# Green_Pill_stlink.net
KiCad netlist of a schematic drawn in EAGLE
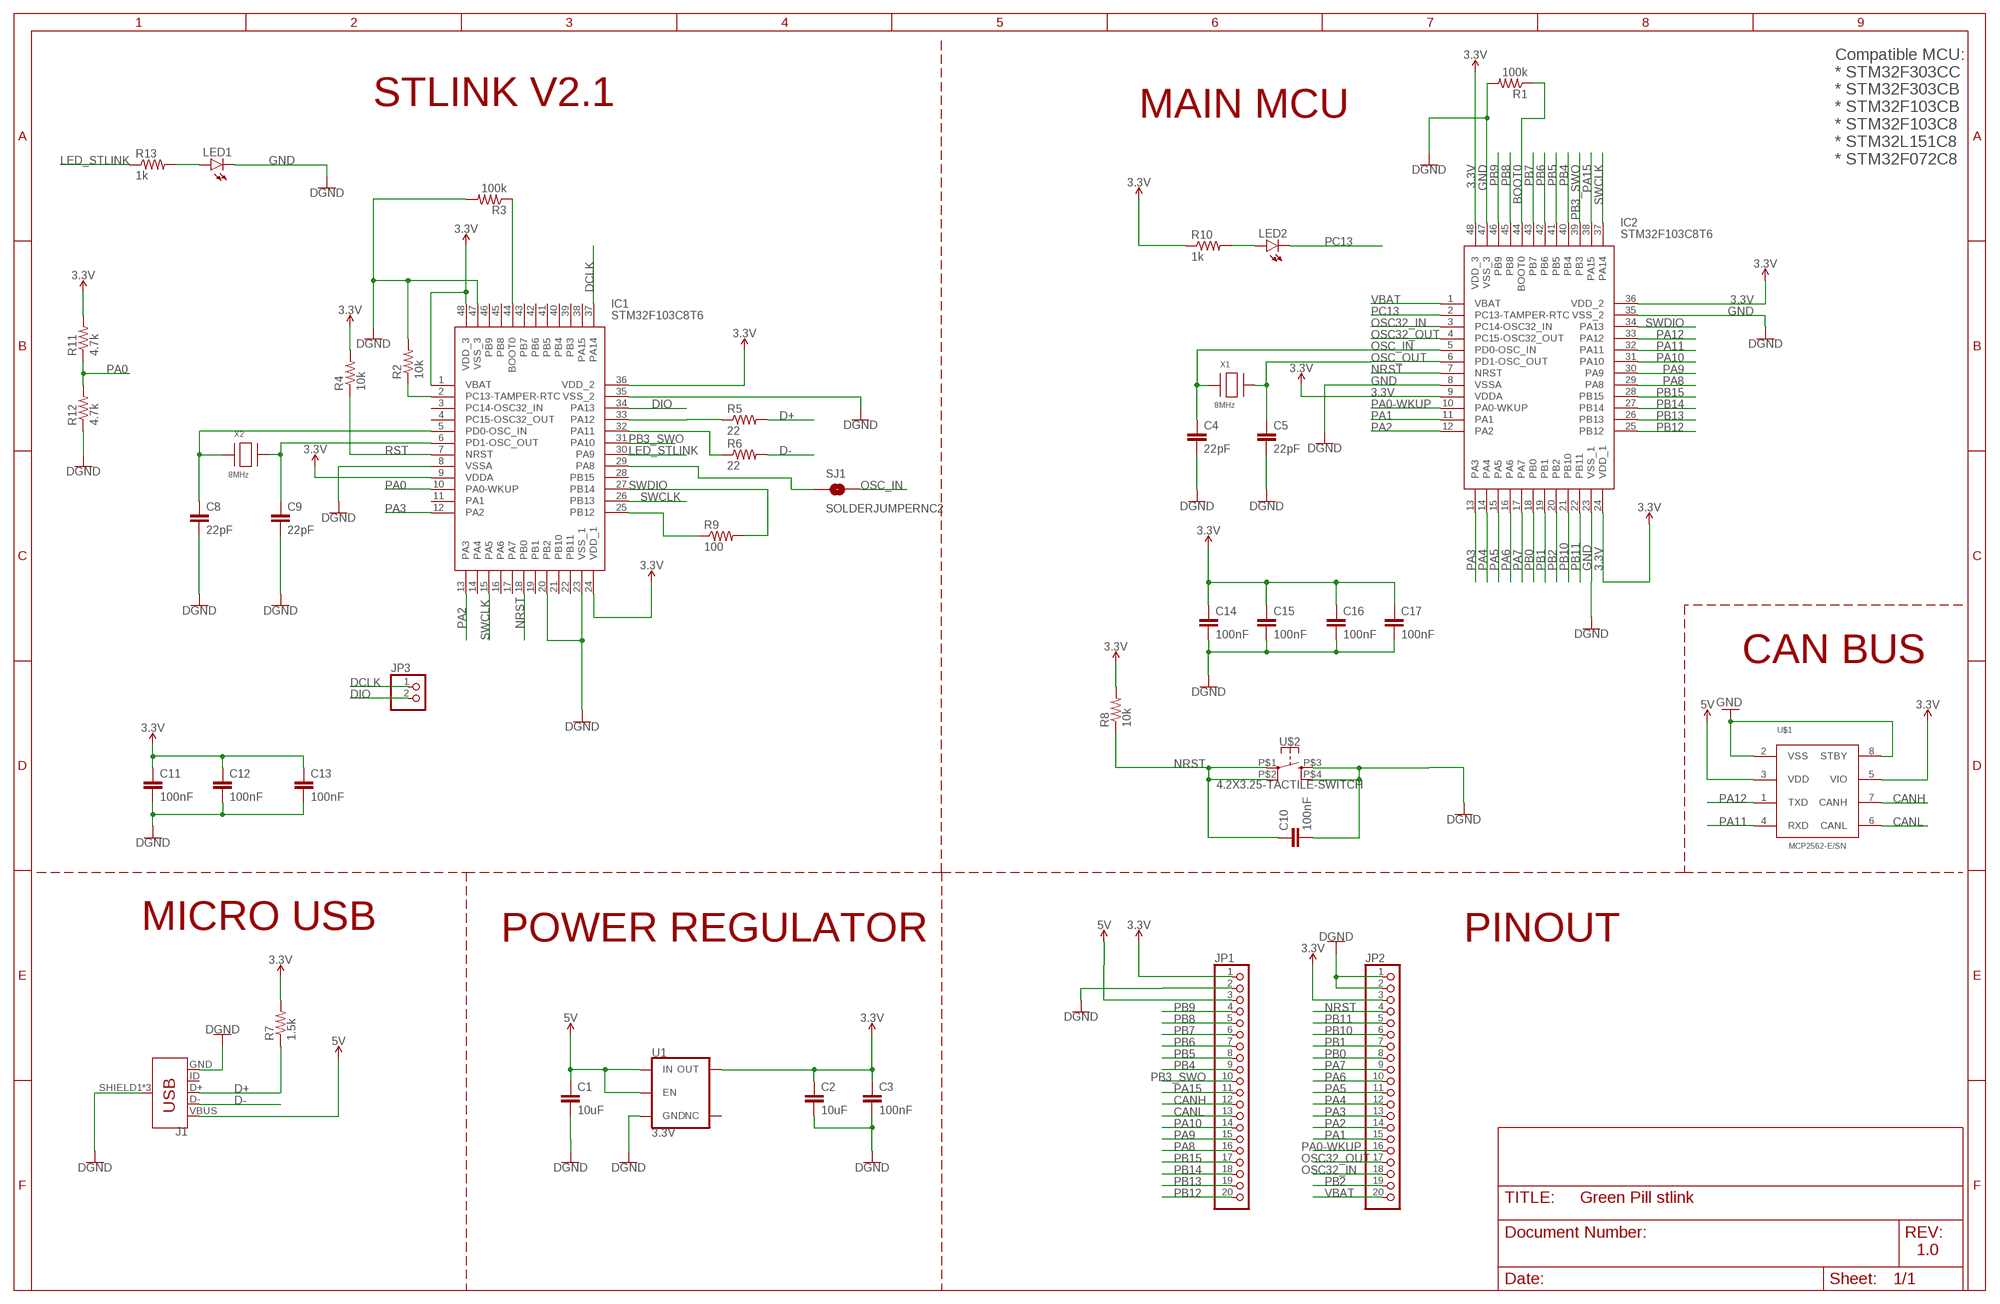
[diagram p0: schematic, sheet 1]

(export (version "E")
  (design (tool "Eeschema 10.0.6"))
  (components
    (comp (ref "C1")
      (value "10uF")
      (footprint "eagle-import:C0805")
      (libsource (lib "eagle-import") (part "C-EUC0805"))
    )
    (comp (ref "C2")
      (value "10uF")
      (footprint "eagle-import:C0805")
      (libsource (lib "eagle-import") (part "C-EUC0805"))
    )
    (comp (ref "C3")
      (value "100nF")
      (footprint "eagle-import:C0603")
      (libsource (lib "eagle-import") (part "C-EUC0603"))
    )
    (comp (ref "C4")
      (value "22pF")
      (footprint "eagle-import:C0603")
      (libsource (lib "eagle-import") (part "resistor_348_C-EUC0603"))
    )
    (comp (ref "C5")
      (value "22pF")
      (footprint "eagle-import:C0603")
      (libsource (lib "eagle-import") (part "resistor_348_C-EUC0603"))
    )
    (comp (ref "C8")
      (value "22pF")
      (footprint "eagle-import:C0603")
      (libsource (lib "eagle-import") (part "resistor_348_C-EUC0603"))
    )
    (comp (ref "C9")
      (value "22pF")
      (footprint "eagle-import:C0603")
      (libsource (lib "eagle-import") (part "resistor_348_C-EUC0603"))
    )
    (comp (ref "C10")
      (value "100nF")
      (footprint "eagle-import:C0603")
      (libsource (lib "eagle-import") (part "C-EUC0603"))
    )
    (comp (ref "C11")
      (value "100nF")
      (footprint "eagle-import:C0603")
      (libsource (lib "eagle-import") (part "C-EUC0603"))
    )
    (comp (ref "C12")
      (value "100nF")
      (footprint "eagle-import:C0603")
      (libsource (lib "eagle-import") (part "C-EUC0603"))
    )
    (comp (ref "C13")
      (value "100nF")
      (footprint "eagle-import:C0603")
      (libsource (lib "eagle-import") (part "C-EUC0603"))
    )
    (comp (ref "C14")
      (value "100nF")
      (footprint "eagle-import:C0603")
      (libsource (lib "eagle-import") (part "C-EUC0603"))
    )
    (comp (ref "C15")
      (value "100nF")
      (footprint "eagle-import:C0603")
      (libsource (lib "eagle-import") (part "C-EUC0603"))
    )
    (comp (ref "C16")
      (value "100nF")
      (footprint "eagle-import:C0603")
      (libsource (lib "eagle-import") (part "C-EUC0603"))
    )
    (comp (ref "C17")
      (value "100nF")
      (footprint "eagle-import:C0603")
      (libsource (lib "eagle-import") (part "C-EUC0603"))
    )
    (comp (ref "IC1")
      (value "STM32F103C8T6")
      (footprint "eagle-import:QFP50P900X900X160-48N")
      (fields (field (name "MOUSER_PART_NUMBER") "511-STM32F103C8T6"))
      (libsource (lib "eagle-import") (part "STM32F103C8T6"))
    )
    (comp (ref "IC2")
      (value "STM32F103C8T6")
      (footprint "eagle-import:QFP50P900X900X160-48N")
      (fields (field (name "MOUSER_PART_NUMBER") "511-STM32F103C8T6"))
      (libsource (lib "eagle-import") (part "STM32F103C8T6"))
    )
    (comp (ref "J1")
      (value "USB_MICRO-B_FEMALE-SMT")
      (footprint "eagle-import:USB-B-MICRO-SMD")
      (libsource (lib "eagle-import") (part "USB_MICRO-B_FEMALE-SMT"))
    )
    (comp (ref "JP1")
      (value "PINHD-1X20")
      (footprint "eagle-import:1X20")
      (libsource (lib "eagle-import") (part "PINHD-1X20"))
    )
    (comp (ref "JP2")
      (value "PINHD-1X20")
      (footprint "eagle-import:1X20")
      (libsource (lib "eagle-import") (part "PINHD-1X20"))
    )
    (comp (ref "JP3")
      (value "PINHD-1X2")
      (footprint "eagle-import:1X02")
      (libsource (lib "eagle-import") (part "PINHD-1X2"))
    )
    (comp (ref "LED1")
      (value "LEDCHIP-LED0805")
      (footprint "eagle-import:CHIP-LED0805")
      (libsource (lib "eagle-import") (part "LEDCHIP-LED0805"))
    )
    (comp (ref "LED2")
      (value "LEDCHIP-LED0805")
      (footprint "eagle-import:CHIP-LED0805")
      (libsource (lib "eagle-import") (part "LEDCHIP-LED0805"))
    )
    (comp (ref "R1")
      (value "100k")
      (footprint "eagle-import:R0603")
      (libsource (lib "eagle-import") (part "R-US_R0603"))
    )
    (comp (ref "R2")
      (value "10k")
      (footprint "eagle-import:R0603")
      (libsource (lib "eagle-import") (part "R-US_R0603"))
    )
    (comp (ref "R3")
      (value "100k")
      (footprint "eagle-import:R0603")
      (libsource (lib "eagle-import") (part "R-US_R0603"))
    )
    (comp (ref "R4")
      (value "10k")
      (footprint "eagle-import:R0603")
      (libsource (lib "eagle-import") (part "R-US_R0603"))
    )
    (comp (ref "R5")
      (value "22")
      (footprint "eagle-import:R0603")
      (libsource (lib "eagle-import") (part "resistor_348_R-US_R0603"))
    )
    (comp (ref "R6")
      (value "22")
      (footprint "eagle-import:R0603")
      (libsource (lib "eagle-import") (part "resistor_348_R-US_R0603"))
    )
    (comp (ref "R7")
      (value "1.5k")
      (footprint "eagle-import:R0603")
      (libsource (lib "eagle-import") (part "resistor_348_R-US_R0603"))
    )
    (comp (ref "R8")
      (value "10k")
      (footprint "eagle-import:R0603")
      (libsource (lib "eagle-import") (part "R-US_R0603"))
    )
    (comp (ref "R9")
      (value "100")
      (footprint "eagle-import:R0603")
      (libsource (lib "eagle-import") (part "R-US_R0603"))
    )
    (comp (ref "R10")
      (value "1k")
      (footprint "eagle-import:R0603")
      (libsource (lib "eagle-import") (part "R-US_R0603"))
    )
    (comp (ref "R11")
      (value "4.7k")
      (footprint "eagle-import:R0603")
      (libsource (lib "eagle-import") (part "R-US_R0603"))
    )
    (comp (ref "R12")
      (value "4.7k")
      (footprint "eagle-import:R0603")
      (libsource (lib "eagle-import") (part "R-US_R0603"))
    )
    (comp (ref "R13")
      (value "1k")
      (footprint "eagle-import:R0603")
      (libsource (lib "eagle-import") (part "R-US_R0603"))
    )
    (comp (ref "SJ1")
      (value "SOLDERJUMPERNC2")
      (footprint "eagle-import:SJ_2S-NOTRACE")
      (libsource (lib "eagle-import") (part "SOLDERJUMPERNC2"))
    )
    (comp (ref "U$1")
      (value "MCP2562-E/SN")
      (footprint "eagle-import:SOIC8")
      (libsource (lib "eagle-import") (part "MCP2562-E/SN"))
    )
    (comp (ref "U$2")
      (value "4.2X3.25-TACTILE-SWITCH")
      (footprint "eagle-import:4.2X3.25")
      (libsource (lib "eagle-import") (part "4.2X3.25-TACTILE-SWITCH"))
    )
    (comp (ref "U1")
      (value "3.3V")
      (footprint "eagle-import:SOT23-5")
      (libsource (lib "eagle-import") (part "V_REG_AP2112K-3.3V"))
    )
    (comp (ref "X1")
      (value "8MHz")
      (footprint "eagle-import:NX5032")
      (libsource (lib "eagle-import") (part "XTALNX5032"))
    )
    (comp (ref "X2")
      (value "8MHz")
      (footprint "eagle-import:NX5032")
      (libsource (lib "eagle-import") (part "XTALNX5032"))
    )
  )
  (nets
    (net (code "1") (name "/BOOT0") (class "Default")
      (node (ref "IC2") (pin "44") (pinfunction "BOOT0_44") (pintype "bidirectional"))
      (node (ref "R1") (pin "1") (pinfunction "1_1") (pintype "passive"))
    )
    (net (code "2") (name "/CANH") (class "Default")
      (node (ref "JP1") (pin "12") (pinfunction "12_12") (pintype "passive"))
      (node (ref "U$1") (pin "7") (pinfunction "CANH_7") (pintype "bidirectional"))
    )
    (net (code "3") (name "/CANL") (class "Default")
      (node (ref "JP1") (pin "13") (pinfunction "13_13") (pintype "passive"))
      (node (ref "U$1") (pin "6") (pinfunction "CANL_6") (pintype "bidirectional"))
    )
    (net (code "4") (name "/D+") (class "Default")
      (node (ref "J1") (pin "D+") (pinfunction "D+_D+") (pintype "bidirectional"))
      (node (ref "R5") (pin "2") (pinfunction "2_2") (pintype "passive"))
      (node (ref "R7") (pin "1") (pinfunction "1_1") (pintype "passive"))
    )
    (net (code "5") (name "/D-") (class "Default")
      (node (ref "J1") (pin "D-") (pinfunction "D-_D-") (pintype "bidirectional"))
      (node (ref "R6") (pin "2") (pinfunction "2_2") (pintype "passive"))
    )
    (net (code "6") (name "/DCLK") (class "Default")
      (node (ref "IC1") (pin "37") (pinfunction "PA14_37") (pintype "bidirectional"))
      (node (ref "JP3") (pin "1") (pinfunction "1_1") (pintype "passive"))
    )
    (net (code "7") (name "/DIO") (class "Default")
      (node (ref "IC1") (pin "34") (pinfunction "PA13_34") (pintype "bidirectional"))
      (node (ref "JP3") (pin "2") (pinfunction "2_2") (pintype "passive"))
    )
    (net (code "8") (name "/LED_STLINK") (class "Default")
      (node (ref "IC1") (pin "30") (pinfunction "PA9_30") (pintype "bidirectional"))
      (node (ref "R13") (pin "1") (pinfunction "1_1") (pintype "passive"))
    )
    (net (code "9") (name "/NRST") (class "Default")
      (node (ref "C10") (pin "1") (pinfunction "1_1") (pintype "passive"))
      (node (ref "IC1") (pin "18") (pinfunction "PB0_18") (pintype "bidirectional"))
      (node (ref "IC2") (pin "7") (pinfunction "NRST_7") (pintype "input"))
      (node (ref "JP2") (pin "4") (pinfunction "4_4") (pintype "passive"))
      (node (ref "R8") (pin "1") (pinfunction "1_1") (pintype "passive"))
      (node (ref "U$2") (pin "P$1") (pinfunction "1_P$1") (pintype "passive"))
      (node (ref "U$2") (pin "P$2") (pinfunction "2_P$2") (pintype "passive"))
    )
    (net (code "10") (name "/OSC32_IN") (class "Default")
      (node (ref "IC2") (pin "3") (pinfunction "PC14-OSC32_IN_3") (pintype "input"))
      (node (ref "JP2") (pin "18") (pinfunction "18_18") (pintype "passive"))
    )
    (net (code "11") (name "/OSC32_OUT") (class "Default")
      (node (ref "IC2") (pin "4") (pinfunction "PC15-OSC32_OUT_4") (pintype "output"))
      (node (ref "JP2") (pin "17") (pinfunction "17_17") (pintype "passive"))
    )
    (net (code "12") (name "/OSC_IN") (class "Default")
      (node (ref "C4") (pin "1") (pinfunction "1_1") (pintype "passive"))
      (node (ref "IC2") (pin "5") (pinfunction "PD0-OSC_IN_5") (pintype "input"))
      (node (ref "SJ1") (pin "2") (pinfunction "2_2") (pintype "passive"))
      (node (ref "X1") (pin "P$1") (pinfunction "P$1_P$1") (pintype "bidirectional"))
    )
    (net (code "13") (name "/OSC_OUT") (class "Default")
      (node (ref "C5") (pin "1") (pinfunction "1_1") (pintype "passive"))
      (node (ref "IC2") (pin "6") (pinfunction "PD1-OSC_OUT_6") (pintype "output"))
      (node (ref "X1") (pin "P$2") (pinfunction "P$2_P$2") (pintype "bidirectional"))
    )
    (net (code "14") (name "/PA0") (class "Default")
      (node (ref "IC1") (pin "10") (pinfunction "PA0-WKUP_10") (pintype "bidirectional"))
      (node (ref "R11") (pin "1") (pinfunction "1_1") (pintype "passive"))
      (node (ref "R12") (pin "2") (pinfunction "2_2") (pintype "passive"))
    )
    (net (code "15") (name "/PA0-WKUP") (class "Default")
      (node (ref "IC2") (pin "10") (pinfunction "PA0-WKUP_10") (pintype "bidirectional"))
      (node (ref "JP2") (pin "16") (pinfunction "16_16") (pintype "passive"))
    )
    (net (code "16") (name "/PA1") (class "Default")
      (node (ref "IC2") (pin "11") (pinfunction "PA1_11") (pintype "bidirectional"))
      (node (ref "JP2") (pin "15") (pinfunction "15_15") (pintype "passive"))
    )
    (net (code "17") (name "/PA2") (class "Default")
      (node (ref "IC1") (pin "13") (pinfunction "PA3_13") (pintype "bidirectional"))
      (node (ref "IC2") (pin "12") (pinfunction "PA2_12") (pintype "bidirectional"))
      (node (ref "JP2") (pin "14") (pinfunction "14_14") (pintype "passive"))
    )
    (net (code "18") (name "/PA3") (class "Default")
      (node (ref "IC1") (pin "12") (pinfunction "PA2_12") (pintype "bidirectional"))
      (node (ref "IC2") (pin "13") (pinfunction "PA3_13") (pintype "bidirectional"))
      (node (ref "JP2") (pin "13") (pinfunction "13_13") (pintype "passive"))
    )
    (net (code "19") (name "/PA4") (class "Default")
      (node (ref "IC2") (pin "14") (pinfunction "PA4_14") (pintype "bidirectional"))
      (node (ref "JP2") (pin "12") (pinfunction "12_12") (pintype "passive"))
    )
    (net (code "20") (name "/PA5") (class "Default")
      (node (ref "IC2") (pin "15") (pinfunction "PA5_15") (pintype "bidirectional"))
      (node (ref "JP2") (pin "11") (pinfunction "11_11") (pintype "passive"))
    )
    (net (code "21") (name "/PA6") (class "Default")
      (node (ref "IC2") (pin "16") (pinfunction "PA6_16") (pintype "bidirectional"))
      (node (ref "JP2") (pin "10") (pinfunction "10_10") (pintype "passive"))
    )
    (net (code "22") (name "/PA7") (class "Default")
      (node (ref "IC2") (pin "17") (pinfunction "PA7_17") (pintype "bidirectional"))
      (node (ref "JP2") (pin "9") (pinfunction "9_9") (pintype "passive"))
    )
    (net (code "23") (name "/PA8") (class "Default")
      (node (ref "IC2") (pin "29") (pinfunction "PA8_29") (pintype "bidirectional"))
      (node (ref "JP1") (pin "16") (pinfunction "16_16") (pintype "passive"))
    )
    (net (code "24") (name "/PA9") (class "Default")
      (node (ref "IC2") (pin "30") (pinfunction "PA9_30") (pintype "bidirectional"))
      (node (ref "JP1") (pin "15") (pinfunction "15_15") (pintype "passive"))
    )
    (net (code "25") (name "/PA10") (class "Default")
      (node (ref "IC2") (pin "31") (pinfunction "PA10_31") (pintype "bidirectional"))
      (node (ref "JP1") (pin "14") (pinfunction "14_14") (pintype "passive"))
    )
    (net (code "26") (name "/PA11") (class "Default")
      (node (ref "IC2") (pin "32") (pinfunction "PA11_32") (pintype "bidirectional"))
      (node (ref "U$1") (pin "4") (pinfunction "RXD_4") (pintype "bidirectional"))
    )
    (net (code "27") (name "/PA12") (class "Default")
      (node (ref "IC2") (pin "33") (pinfunction "PA12_33") (pintype "bidirectional"))
      (node (ref "U$1") (pin "1") (pinfunction "TXD_1") (pintype "bidirectional"))
    )
    (net (code "28") (name "/PA15") (class "Default")
      (node (ref "IC2") (pin "38") (pinfunction "PA15_38") (pintype "bidirectional"))
      (node (ref "JP1") (pin "11") (pinfunction "11_11") (pintype "passive"))
    )
    (net (code "29") (name "/PB0") (class "Default")
      (node (ref "IC2") (pin "18") (pinfunction "PB0_18") (pintype "bidirectional"))
      (node (ref "JP2") (pin "8") (pinfunction "8_8") (pintype "passive"))
    )
    (net (code "30") (name "/PB1") (class "Default")
      (node (ref "IC2") (pin "19") (pinfunction "PB1_19") (pintype "bidirectional"))
      (node (ref "JP2") (pin "7") (pinfunction "7_7") (pintype "passive"))
    )
    (net (code "31") (name "/PB2") (class "Default")
      (node (ref "IC2") (pin "20") (pinfunction "PB2_20") (pintype "bidirectional"))
      (node (ref "JP2") (pin "19") (pinfunction "19_19") (pintype "passive"))
    )
    (net (code "32") (name "/PB3_SWO") (class "Default")
      (node (ref "IC1") (pin "31") (pinfunction "PA10_31") (pintype "bidirectional"))
      (node (ref "IC2") (pin "39") (pinfunction "PB3_39") (pintype "bidirectional"))
      (node (ref "JP1") (pin "10") (pinfunction "10_10") (pintype "passive"))
    )
    (net (code "33") (name "/PB4") (class "Default")
      (node (ref "IC2") (pin "40") (pinfunction "PB4_40") (pintype "bidirectional"))
      (node (ref "JP1") (pin "9") (pinfunction "9_9") (pintype "passive"))
    )
    (net (code "34") (name "/PB5") (class "Default")
      (node (ref "IC2") (pin "41") (pinfunction "PB5_41") (pintype "bidirectional"))
      (node (ref "JP1") (pin "8") (pinfunction "8_8") (pintype "passive"))
    )
    (net (code "35") (name "/PB6") (class "Default")
      (node (ref "IC2") (pin "42") (pinfunction "PB6_42") (pintype "bidirectional"))
      (node (ref "JP1") (pin "7") (pinfunction "7_7") (pintype "passive"))
    )
    (net (code "36") (name "/PB7") (class "Default")
      (node (ref "IC2") (pin "43") (pinfunction "PB7_43") (pintype "bidirectional"))
      (node (ref "JP1") (pin "6") (pinfunction "6_6") (pintype "passive"))
    )
    (net (code "37") (name "/PB8") (class "Default")
      (node (ref "IC2") (pin "45") (pinfunction "PB8_45") (pintype "bidirectional"))
      (node (ref "JP1") (pin "5") (pinfunction "5_5") (pintype "passive"))
    )
    (net (code "38") (name "/PB9") (class "Default")
      (node (ref "IC2") (pin "46") (pinfunction "PB9_46") (pintype "bidirectional"))
      (node (ref "JP1") (pin "4") (pinfunction "4_4") (pintype "passive"))
    )
    (net (code "39") (name "/PB10") (class "Default")
      (node (ref "IC2") (pin "21") (pinfunction "PB10_21") (pintype "bidirectional"))
      (node (ref "JP2") (pin "6") (pinfunction "6_6") (pintype "passive"))
    )
    (net (code "40") (name "/PB11") (class "Default")
      (node (ref "IC2") (pin "22") (pinfunction "PB11_22") (pintype "bidirectional"))
      (node (ref "JP2") (pin "5") (pinfunction "5_5") (pintype "passive"))
    )
    (net (code "41") (name "/PB12") (class "Default")
      (node (ref "IC2") (pin "25") (pinfunction "PB12_25") (pintype "bidirectional"))
      (node (ref "JP1") (pin "20") (pinfunction "20_20") (pintype "passive"))
    )
    (net (code "42") (name "/PB13") (class "Default")
      (node (ref "IC2") (pin "26") (pinfunction "PB13_26") (pintype "bidirectional"))
      (node (ref "JP1") (pin "19") (pinfunction "19_19") (pintype "passive"))
    )
    (net (code "43") (name "/PB14") (class "Default")
      (node (ref "IC2") (pin "27") (pinfunction "PB14_27") (pintype "bidirectional"))
      (node (ref "JP1") (pin "18") (pinfunction "18_18") (pintype "passive"))
    )
    (net (code "44") (name "/PB15") (class "Default")
      (node (ref "IC2") (pin "28") (pinfunction "PB15_28") (pintype "bidirectional"))
      (node (ref "JP1") (pin "17") (pinfunction "17_17") (pintype "passive"))
    )
    (net (code "45") (name "/PC13") (class "Default")
      (node (ref "IC2") (pin "2") (pinfunction "PC13-TAMPER-RTC_2") (pintype "bidirectional"))
      (node (ref "LED2") (pin "C") (pinfunction "C_C") (pintype "passive"))
    )
    (net (code "46") (name "/RST") (class "Default")
      (node (ref "IC1") (pin "7") (pinfunction "NRST_7") (pintype "input"))
      (node (ref "R4") (pin "1") (pinfunction "1_1") (pintype "passive"))
    )
    (net (code "47") (name "/SWCLK") (class "Default")
      (node (ref "IC1") (pin "15") (pinfunction "PA5_15") (pintype "bidirectional"))
      (node (ref "IC1") (pin "26") (pinfunction "PB13_26") (pintype "bidirectional"))
      (node (ref "IC2") (pin "37") (pinfunction "PA14_37") (pintype "bidirectional"))
    )
    (net (code "48") (name "/SWDIO") (class "Default")
      (node (ref "IC1") (pin "27") (pinfunction "PB14_27") (pintype "bidirectional"))
      (node (ref "IC2") (pin "34") (pinfunction "PA13_34") (pintype "bidirectional"))
      (node (ref "R9") (pin "2") (pinfunction "2_2") (pintype "passive"))
    )
    (net (code "49") (name "/VBAT") (class "Default")
      (node (ref "IC2") (pin "1") (pinfunction "VBAT_1") (pintype "bidirectional"))
      (node (ref "JP2") (pin "20") (pinfunction "20_20") (pintype "passive"))
    )
    (net (code "50") (name "3.3V") (class "Default")
      (node (ref "C11") (pin "1") (pinfunction "1_1") (pintype "passive"))
      (node (ref "C12") (pin "1") (pinfunction "1_1") (pintype "passive"))
      (node (ref "C13") (pin "1") (pinfunction "1_1") (pintype "passive"))
      (node (ref "C14") (pin "1") (pinfunction "1_1") (pintype "passive"))
      (node (ref "C15") (pin "1") (pinfunction "1_1") (pintype "passive"))
      (node (ref "C16") (pin "1") (pinfunction "1_1") (pintype "passive"))
      (node (ref "C17") (pin "1") (pinfunction "1_1") (pintype "passive"))
      (node (ref "C2") (pin "1") (pinfunction "1_1") (pintype "passive"))
      (node (ref "C3") (pin "1") (pinfunction "1_1") (pintype "passive"))
      (node (ref "IC1") (pin "1") (pinfunction "VBAT_1") (pintype "bidirectional"))
      (node (ref "IC1") (pin "24") (pinfunction "VDD_1_24") (pintype "power_in"))
      (node (ref "IC1") (pin "36") (pinfunction "VDD_2_36") (pintype "power_in"))
      (node (ref "IC1") (pin "48") (pinfunction "VDD_3_48") (pintype "power_in"))
      (node (ref "IC1") (pin "9") (pinfunction "VDDA_9") (pintype "power_in"))
      (node (ref "IC2") (pin "24") (pinfunction "VDD_1_24") (pintype "power_in"))
      (node (ref "IC2") (pin "36") (pinfunction "VDD_2_36") (pintype "power_in"))
      (node (ref "IC2") (pin "48") (pinfunction "VDD_3_48") (pintype "power_in"))
      (node (ref "IC2") (pin "9") (pinfunction "VDDA_9") (pintype "power_in"))
      (node (ref "JP1") (pin "1") (pinfunction "1_1") (pintype "passive"))
      (node (ref "JP2") (pin "3") (pinfunction "3_3") (pintype "passive"))
      (node (ref "R10") (pin "1") (pinfunction "1_1") (pintype "passive"))
      (node (ref "R11") (pin "2") (pinfunction "2_2") (pintype "passive"))
      (node (ref "R4") (pin "2") (pinfunction "2_2") (pintype "passive"))
      (node (ref "R7") (pin "2") (pinfunction "2_2") (pintype "passive"))
      (node (ref "R8") (pin "2") (pinfunction "2_2") (pintype "passive"))
      (node (ref "U$1") (pin "5") (pinfunction "VIO_5") (pintype "bidirectional"))
      (node (ref "U1") (pin "5") (pinfunction "OUT_5") (pintype "passive"))
    )
    (net (code "51") (name "5V") (class "Default")
      (node (ref "C1") (pin "1") (pinfunction "1_1") (pintype "passive"))
      (node (ref "J1") (pin "VBUS") (pinfunction "VBUS_VBUS") (pintype "power_in"))
      (node (ref "JP1") (pin "3") (pinfunction "3_3") (pintype "passive"))
      (node (ref "U$1") (pin "3") (pinfunction "VDD_3") (pintype "bidirectional"))
      (node (ref "U1") (pin "1") (pinfunction "IN_1") (pintype "input"))
      (node (ref "U1") (pin "3") (pinfunction "EN_3") (pintype "input"))
    )
    (net (code "52") (name "DGND") (class "Default")
      (node (ref "C1") (pin "2") (pinfunction "2_2") (pintype "passive"))
      (node (ref "C10") (pin "2") (pinfunction "2_2") (pintype "passive"))
      (node (ref "C11") (pin "2") (pinfunction "2_2") (pintype "passive"))
      (node (ref "C12") (pin "2") (pinfunction "2_2") (pintype "passive"))
      (node (ref "C13") (pin "2") (pinfunction "2_2") (pintype "passive"))
      (node (ref "C14") (pin "2") (pinfunction "2_2") (pintype "passive"))
      (node (ref "C15") (pin "2") (pinfunction "2_2") (pintype "passive"))
      (node (ref "C16") (pin "2") (pinfunction "2_2") (pintype "passive"))
      (node (ref "C17") (pin "2") (pinfunction "2_2") (pintype "passive"))
      (node (ref "C2") (pin "2") (pinfunction "2_2") (pintype "passive"))
      (node (ref "C3") (pin "2") (pinfunction "2_2") (pintype "passive"))
      (node (ref "C4") (pin "2") (pinfunction "2_2") (pintype "passive"))
      (node (ref "C5") (pin "2") (pinfunction "2_2") (pintype "passive"))
      (node (ref "C8") (pin "2") (pinfunction "2_2") (pintype "passive"))
      (node (ref "C9") (pin "2") (pinfunction "2_2") (pintype "passive"))
      (node (ref "IC1") (pin "20") (pinfunction "PB2_20") (pintype "bidirectional"))
      (node (ref "IC1") (pin "23") (pinfunction "VSS_1_23") (pintype "power_in"))
      (node (ref "IC1") (pin "35") (pinfunction "VSS_2_35") (pintype "power_in"))
      (node (ref "IC1") (pin "47") (pinfunction "VSS_3_47") (pintype "power_in"))
      (node (ref "IC1") (pin "8") (pinfunction "VSSA_8") (pintype "power_in"))
      (node (ref "IC2") (pin "23") (pinfunction "VSS_1_23") (pintype "power_in"))
      (node (ref "IC2") (pin "35") (pinfunction "VSS_2_35") (pintype "power_in"))
      (node (ref "IC2") (pin "47") (pinfunction "VSS_3_47") (pintype "power_in"))
      (node (ref "IC2") (pin "8") (pinfunction "VSSA_8") (pintype "power_in"))
      (node (ref "J1") (pin "GND") (pinfunction "GND_GND") (pintype "power_in"))
      (node (ref "J1") (pin "SHIELD1") (pinfunction "SHIELD_SHIELD1") (pintype "bidirectional"))
      (node (ref "J1") (pin "SHIELD2") (pinfunction "SHIELD_SHIELD2") (pintype "bidirectional"))
      (node (ref "J1") (pin "SHIELD3") (pinfunction "SHIELD_SHIELD3") (pintype "bidirectional"))
      (node (ref "JP1") (pin "2") (pinfunction "2_2") (pintype "passive"))
      (node (ref "JP2") (pin "1") (pinfunction "1_1") (pintype "passive"))
      (node (ref "JP2") (pin "2") (pinfunction "2_2") (pintype "passive"))
      (node (ref "LED1") (pin "C") (pinfunction "C_C") (pintype "passive"))
      (node (ref "R1") (pin "2") (pinfunction "2_2") (pintype "passive"))
      (node (ref "R12") (pin "1") (pinfunction "1_1") (pintype "passive"))
      (node (ref "R2") (pin "2") (pinfunction "2_2") (pintype "passive"))
      (node (ref "R3") (pin "2") (pinfunction "2_2") (pintype "passive"))
      (node (ref "U$1") (pin "2") (pinfunction "VSS_2") (pintype "bidirectional"))
      (node (ref "U$1") (pin "8") (pinfunction "STBY_8") (pintype "bidirectional"))
      (node (ref "U$2") (pin "P$3") (pinfunction "3_P$3") (pintype "passive"))
      (node (ref "U$2") (pin "P$4") (pinfunction "4_P$4") (pintype "passive"))
      (node (ref "U1") (pin "2") (pinfunction "GND_2") (pintype "input"))
    )
    (net (code "53") (name "Net-(IC1-BOOT0)") (class "Default")
      (node (ref "IC1") (pin "44") (pinfunction "BOOT0_44") (pintype "bidirectional"))
      (node (ref "R3") (pin "1") (pinfunction "1_1") (pintype "passive"))
    )
    (net (code "54") (name "Net-(IC1-PA8)") (class "Default")
      (node (ref "IC1") (pin "29") (pinfunction "PA8_29") (pintype "bidirectional"))
      (node (ref "SJ1") (pin "1") (pinfunction "1_1") (pintype "passive"))
    )
    (net (code "55") (name "Net-(IC1-PA11)") (class "Default")
      (node (ref "IC1") (pin "32") (pinfunction "PA11_32") (pintype "bidirectional"))
      (node (ref "R6") (pin "1") (pinfunction "1_1") (pintype "passive"))
    )
    (net (code "56") (name "Net-(IC1-PA12)") (class "Default")
      (node (ref "IC1") (pin "33") (pinfunction "PA12_33") (pintype "bidirectional"))
      (node (ref "R5") (pin "1") (pinfunction "1_1") (pintype "passive"))
    )
    (net (code "57") (name "Net-(IC1-PB12)") (class "Default")
      (node (ref "IC1") (pin "25") (pinfunction "PB12_25") (pintype "bidirectional"))
      (node (ref "R9") (pin "1") (pinfunction "1_1") (pintype "passive"))
    )
    (net (code "58") (name "Net-(IC1-PC13-TAMPER-RTC)") (class "Default")
      (node (ref "IC1") (pin "2") (pinfunction "PC13-TAMPER-RTC_2") (pintype "bidirectional"))
      (node (ref "R2") (pin "1") (pinfunction "1_1") (pintype "passive"))
    )
    (net (code "59") (name "Net-(IC1-PD0-OSC_IN)") (class "Default")
      (node (ref "C8") (pin "1") (pinfunction "1_1") (pintype "passive"))
      (node (ref "IC1") (pin "5") (pinfunction "PD0-OSC_IN_5") (pintype "input"))
      (node (ref "X2") (pin "P$1") (pinfunction "P$1_P$1") (pintype "bidirectional"))
    )
    (net (code "60") (name "Net-(IC1-PD1-OSC_OUT)") (class "Default")
      (node (ref "C9") (pin "1") (pinfunction "1_1") (pintype "passive"))
      (node (ref "IC1") (pin "6") (pinfunction "PD1-OSC_OUT_6") (pintype "output"))
      (node (ref "X2") (pin "P$2") (pinfunction "P$2_P$2") (pintype "bidirectional"))
    )
    (net (code "61") (name "Net-(LED1-PadA)") (class "Default")
      (node (ref "LED1") (pin "A") (pinfunction "A_A") (pintype "passive"))
      (node (ref "R13") (pin "2") (pinfunction "2_2") (pintype "passive"))
    )
    (net (code "62") (name "Net-(LED2-PadA)") (class "Default")
      (node (ref "LED2") (pin "A") (pinfunction "A_A") (pintype "passive"))
      (node (ref "R10") (pin "2") (pinfunction "2_2") (pintype "passive"))
    )
    (net (code "63") (name "unconnected-(IC1-PA1-Pad11)") (class "Default")
      (node (ref "IC1") (pin "11") (pinfunction "PA1_11") (pintype "bidirectional"))
    )
    (net (code "64") (name "unconnected-(IC1-PA4-Pad14)") (class "Default")
      (node (ref "IC1") (pin "14") (pinfunction "PA4_14") (pintype "bidirectional"))
    )
    (net (code "65") (name "unconnected-(IC1-PA6-Pad16)") (class "Default")
      (node (ref "IC1") (pin "16") (pinfunction "PA6_16") (pintype "bidirectional"))
    )
    (net (code "66") (name "unconnected-(IC1-PA7-Pad17)") (class "Default")
      (node (ref "IC1") (pin "17") (pinfunction "PA7_17") (pintype "bidirectional"))
    )
    (net (code "67") (name "unconnected-(IC1-PA15-Pad38)") (class "Default")
      (node (ref "IC1") (pin "38") (pinfunction "PA15_38") (pintype "bidirectional"))
    )
    (net (code "68") (name "unconnected-(IC1-PB1-Pad19)") (class "Default")
      (node (ref "IC1") (pin "19") (pinfunction "PB1_19") (pintype "bidirectional"))
    )
    (net (code "69") (name "unconnected-(IC1-PB3-Pad39)") (class "Default")
      (node (ref "IC1") (pin "39") (pinfunction "PB3_39") (pintype "bidirectional"))
    )
    (net (code "70") (name "unconnected-(IC1-PB4-Pad40)") (class "Default")
      (node (ref "IC1") (pin "40") (pinfunction "PB4_40") (pintype "bidirectional"))
    )
    (net (code "71") (name "unconnected-(IC1-PB5-Pad41)") (class "Default")
      (node (ref "IC1") (pin "41") (pinfunction "PB5_41") (pintype "bidirectional"))
    )
    (net (code "72") (name "unconnected-(IC1-PB6-Pad42)") (class "Default")
      (node (ref "IC1") (pin "42") (pinfunction "PB6_42") (pintype "bidirectional"))
    )
    (net (code "73") (name "unconnected-(IC1-PB7-Pad43)") (class "Default")
      (node (ref "IC1") (pin "43") (pinfunction "PB7_43") (pintype "bidirectional"))
    )
    (net (code "74") (name "unconnected-(IC1-PB8-Pad45)") (class "Default")
      (node (ref "IC1") (pin "45") (pinfunction "PB8_45") (pintype "bidirectional"))
    )
    (net (code "75") (name "unconnected-(IC1-PB9-Pad46)") (class "Default")
      (node (ref "IC1") (pin "46") (pinfunction "PB9_46") (pintype "bidirectional"))
    )
    (net (code "76") (name "unconnected-(IC1-PB10-Pad21)") (class "Default")
      (node (ref "IC1") (pin "21") (pinfunction "PB10_21") (pintype "bidirectional"))
    )
    (net (code "77") (name "unconnected-(IC1-PB11-Pad22)") (class "Default")
      (node (ref "IC1") (pin "22") (pinfunction "PB11_22") (pintype "bidirectional"))
    )
    (net (code "78") (name "unconnected-(IC1-PB15-Pad28)") (class "Default")
      (node (ref "IC1") (pin "28") (pinfunction "PB15_28") (pintype "bidirectional"))
    )
    (net (code "79") (name "unconnected-(IC1-PC14-OSC32_IN-Pad3)") (class "Default")
      (node (ref "IC1") (pin "3") (pinfunction "PC14-OSC32_IN_3") (pintype "input"))
    )
    (net (code "80") (name "unconnected-(IC1-PC15-OSC32_OUT-Pad4)") (class "Default")
      (node (ref "IC1") (pin "4") (pinfunction "PC15-OSC32_OUT_4") (pintype "output"))
    )
    (net (code "81") (name "unconnected-(J1-PadID)") (class "Default")
      (node (ref "J1") (pin "ID") (pinfunction "ID_ID") (pintype "bidirectional"))
    )
    (net (code "82") (name "unconnected-(U1-NC-Pad4)") (class "Default")
      (node (ref "U1") (pin "4") (pinfunction "NC_4") (pintype "no_connect"))
    )
  )
)
